# STB_LightSensors.net
KiCad netlist of a schematic drawn in Altium Designer
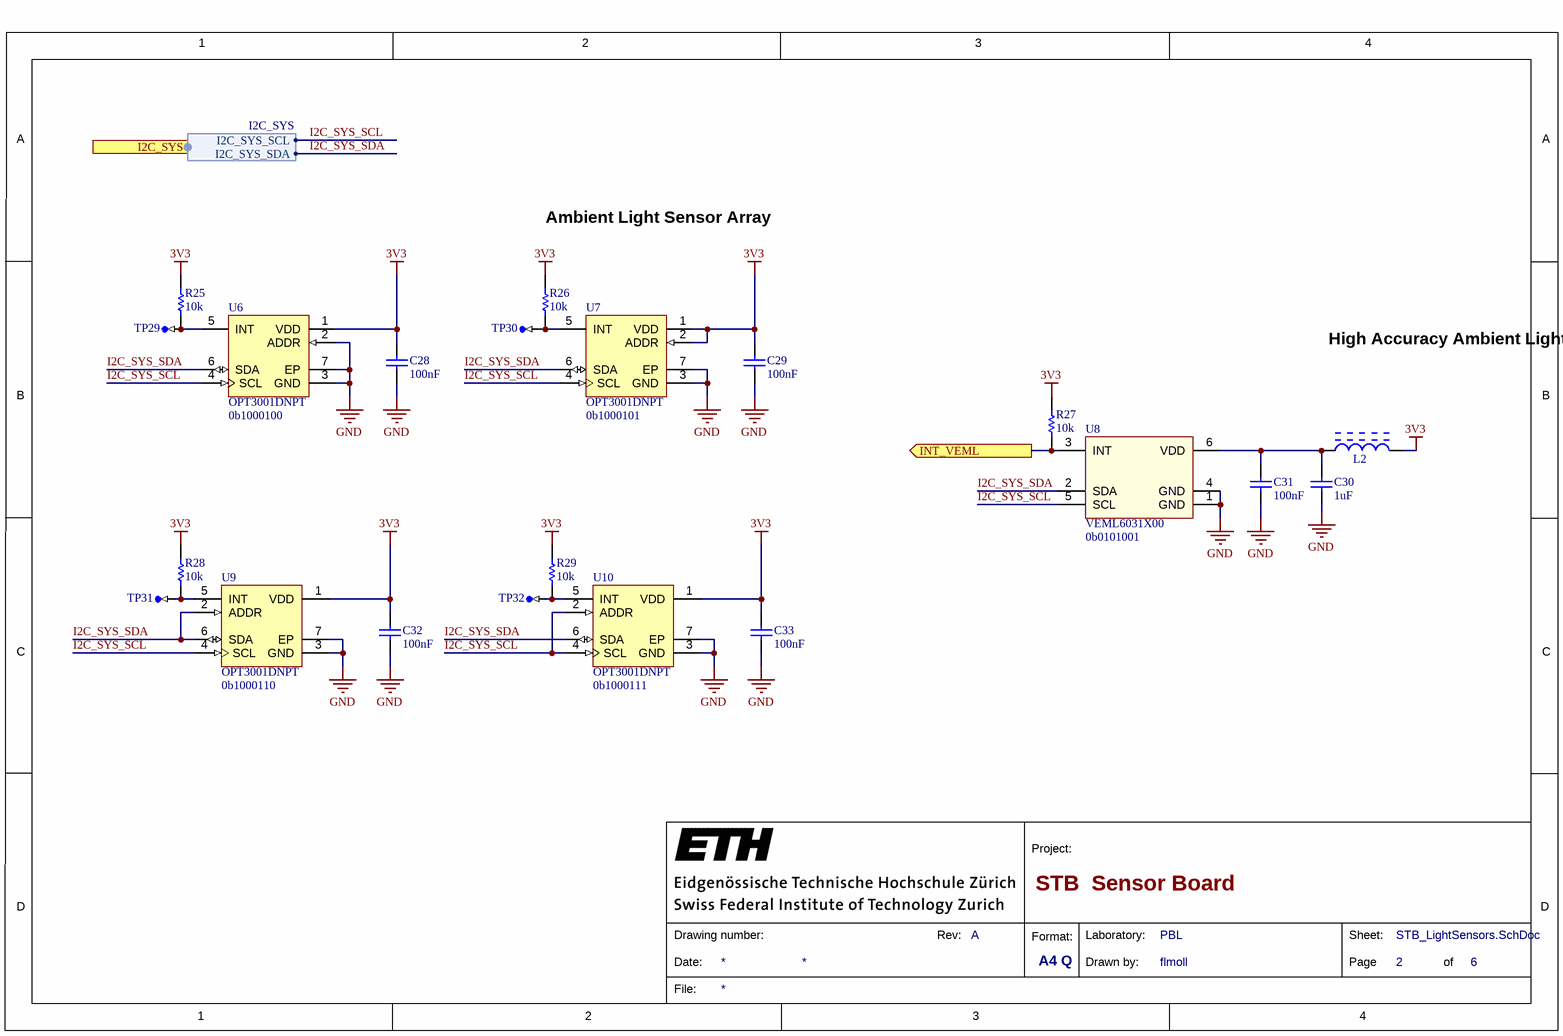
[diagram p0: STB_LightSensors.SchDoc]

(export (version "E")
  (design (tool "Eeschema 10.0.6"))
  (components
    (comp (ref "C28")
      (value "100nF")
      (footprint "CAPC1050X55X23LL05T13")
      (description "Chip Capacitor, 100 nF, +/- 10%, 16 V, -55 to 125 degC, 0402 (1005 Metric), RoHS, Tape and Reel")
      (fields
        (field (name "MANUFACTURER") "Samsung Electro-Mechanics")
        (field (name "MANUFACTURER PART NUMBER") "CL05B104KO5NNNC")
      )
      (libsource (lib "Altium Content Vault") (part "CAP-NP-2"))
    )
    (comp (ref "C29")
      (value "100nF")
      (footprint "CAPC1050X55X23LL05T13")
      (description "Chip Capacitor, 100 nF, +/- 10%, 16 V, -55 to 125 degC, 0402 (1005 Metric), RoHS, Tape and Reel")
      (fields
        (field (name "MANUFACTURER") "Samsung Electro-Mechanics")
        (field (name "MANUFACTURER PART NUMBER") "CL05B104KO5NNNC")
      )
      (libsource (lib "Altium Content Vault") (part "CAP-NP-2"))
    )
    (comp (ref "C30")
      (value "1uF")
      (footprint "CAPC1608X90X35LL15T15")
      (fields (field (name "MANUFACTURER") "Kemet") (field (name "PART NUMBER") "C0603C105K4RACTU"))
      (libsource (lib "Altium Content Vault") (part "CAP"))
    )
    (comp (ref "C31")
      (value "100nF")
      (footprint "CAPC1050X55X23LL05T13")
      (description "Chip Capacitor, 100 nF, +/- 10%, 16 V, -55 to 125 degC, 0402 (1005 Metric), RoHS, Tape and Reel")
      (fields
        (field (name "MANUFACTURER") "Samsung Electro-Mechanics")
        (field (name "MANUFACTURER PART NUMBER") "CL05B104KO5NNNC")
      )
      (libsource (lib "Altium Content Vault") (part "CAP-NP-2"))
    )
    (comp (ref "C32")
      (value "100nF")
      (footprint "CAPC1050X55X23LL05T13")
      (description "Chip Capacitor, 100 nF, +/- 10%, 16 V, -55 to 125 degC, 0402 (1005 Metric), RoHS, Tape and Reel")
      (fields
        (field (name "MANUFACTURER") "Samsung Electro-Mechanics")
        (field (name "MANUFACTURER PART NUMBER") "CL05B104KO5NNNC")
      )
      (libsource (lib "Altium Content Vault") (part "CAP-NP-2"))
    )
    (comp (ref "C33")
      (value "100nF")
      (footprint "CAPC1050X55X23LL05T13")
      (description "Chip Capacitor, 100 nF, +/- 10%, 16 V, -55 to 125 degC, 0402 (1005 Metric), RoHS, Tape and Reel")
      (fields
        (field (name "MANUFACTURER") "Samsung Electro-Mechanics")
        (field (name "MANUFACTURER PART NUMBER") "CL05B104KO5NNNC")
      )
      (libsource (lib "Altium Content Vault") (part "CAP-NP-2"))
    )
    (comp (ref "L2")
      (value "LI0402E300R-10")
      (footprint "INDC1005X07L")
      (description "30 Ohm 1 Power, Signal Line Ferrite Bead 0402 (1005 Metric) 500mA 300 mOhm Max DCR")
      (fields (field (name "MANUFACTURER") "Laird-Signal Integrity Products"))
      (libsource (lib "ETHZ Vault") (part "Ferrite Bead"))
    )
    (comp (ref "R25")
      (value "10k")
      (footprint "RESC1005X40X25LL05T05")
      (description "Chip Resistor, 10 KOhm, +/- 1%, 0.1 W, -55 to 155 degC, 0402 (1005 Metric), RoHS, Tape and Reel")
      (fields (field (name "TOLERANCE") "1%") (field (name "MANUFACTURER") "Panasonic"))
      (libsource (lib "Altium Content Vault") (part "RES-2"))
    )
    (comp (ref "R26")
      (value "10k")
      (footprint "RESC1005X40X25LL05T05")
      (description "Chip Resistor, 10 KOhm, +/- 1%, 0.1 W, -55 to 155 degC, 0402 (1005 Metric), RoHS, Tape and Reel")
      (fields (field (name "TOLERANCE") "1%") (field (name "MANUFACTURER") "Panasonic"))
      (libsource (lib "Altium Content Vault") (part "RES-2"))
    )
    (comp (ref "R27")
      (value "10k")
      (footprint "RESC1005X40X25LL05T05")
      (description "Chip Resistor, 10 KOhm, +/- 1%, 0.1 W, -55 to 155 degC, 0402 (1005 Metric), RoHS, Tape and Reel")
      (fields (field (name "TOLERANCE") "1%") (field (name "MANUFACTURER") "Panasonic"))
      (libsource (lib "Altium Content Vault") (part "RES-2"))
    )
    (comp (ref "R28")
      (value "10k")
      (footprint "RESC1005X40X25LL05T05")
      (description "Chip Resistor, 10 KOhm, +/- 1%, 0.1 W, -55 to 155 degC, 0402 (1005 Metric), RoHS, Tape and Reel")
      (fields (field (name "TOLERANCE") "1%") (field (name "MANUFACTURER") "Panasonic"))
      (libsource (lib "Altium Content Vault") (part "RES-2"))
    )
    (comp (ref "R29")
      (value "10k")
      (footprint "RESC1005X40X25LL05T05")
      (description "Chip Resistor, 10 KOhm, +/- 1%, 0.1 W, -55 to 155 degC, 0402 (1005 Metric), RoHS, Tape and Reel")
      (fields (field (name "TOLERANCE") "1%") (field (name "MANUFACTURER") "Panasonic"))
      (libsource (lib "Altium Content Vault") (part "RES-2"))
    )
    (comp (ref "TP29")
      (value "testPoint_1mm")
      (footprint "TP-SM-C-100")
      (description "testPoint 1mm")
      (libsource (lib "STB_Schlib") (part "testPoint_1mm"))
    )
    (comp (ref "TP30")
      (value "testPoint_1mm")
      (footprint "TP-SM-C-100")
      (description "testPoint 1mm")
      (libsource (lib "STB_Schlib") (part "testPoint_1mm"))
    )
    (comp (ref "TP31")
      (value "testPoint_1mm")
      (footprint "TP-SM-C-100")
      (description "testPoint 1mm")
      (libsource (lib "STB_Schlib") (part "testPoint_1mm"))
    )
    (comp (ref "TP32")
      (value "testPoint_1mm")
      (footprint "TP-SM-C-100")
      (description "testPoint 1mm")
      (libsource (lib "STB_Schlib") (part "testPoint_1mm"))
    )
    (comp (ref "U6")
      (value "OPT3001DNPT")
      (footprint "DNP0006A")
      (fields (field (name "MANUFACTURER") "Texas Instruments"))
      (libsource (lib "Altium Content Vault") (part "TI-OPT3001-DNP-6"))
    )
    (comp (ref "U7")
      (value "OPT3001DNPT")
      (footprint "DNP0006A")
      (fields (field (name "MANUFACTURER") "Texas Instruments"))
      (libsource (lib "Altium Content Vault") (part "TI-OPT3001-DNP-6"))
    )
    (comp (ref "U8")
      (value "VEML6031X00")
      (footprint "6-SMD - No Thermal Pad_2")
      (description "Ambient Light Sensor, I²C 6-SMD, No Lead")
      (fields
        (field (name "MFR") "Vishay Semiconductor Opto Division")
        (field (name "MANUFACTURER") "Vishay")
      )
      (libsource (lib "ETHZ Vault") (part "VEML60311X00"))
    )
    (comp (ref "U9")
      (value "OPT3001DNPT")
      (footprint "DNP0006A")
      (fields (field (name "MANUFACTURER") "Texas Instruments"))
      (libsource (lib "") (part "TI-OPT3001-DNP-6_1"))
    )
    (comp (ref "U10")
      (value "OPT3001DNPT")
      (footprint "DNP0006A")
      (fields (field (name "MANUFACTURER") "Texas Instruments"))
      (libsource (lib "") (part "TI-OPT3001-DNP-6_1"))
    )
  )
  (nets
    (net (code "2") (name "/I2C_SYS_SCL") (class "Default")
      (node (ref "U10") (pin "2") (pinfunction "ADDR_2") (pintype "input"))
      (node (ref "U10") (pin "4") (pinfunction "SCL_4") (pintype "input"))
      (node (ref "U6") (pin "4") (pinfunction "SCL_4") (pintype "input"))
      (node (ref "U7") (pin "4") (pinfunction "SCL_4") (pintype "input"))
      (node (ref "U8") (pin "5") (pinfunction "SCL_5") (pintype "passive"))
      (node (ref "U9") (pin "4") (pinfunction "SCL_4") (pintype "input"))
    )
    (net (code "3") (name "/I2C_SYS_SDA") (class "Default")
      (node (ref "U10") (pin "6") (pinfunction "SDA_6") (pintype "bidirectional"))
      (node (ref "U6") (pin "6") (pinfunction "SDA_6") (pintype "bidirectional"))
      (node (ref "U7") (pin "6") (pinfunction "SDA_6") (pintype "bidirectional"))
      (node (ref "U8") (pin "2") (pinfunction "SDA_2") (pintype "passive"))
      (node (ref "U9") (pin "2") (pinfunction "ADDR_2") (pintype "input"))
      (node (ref "U9") (pin "6") (pinfunction "SDA_6") (pintype "bidirectional"))
    )
    (net (code "4") (name "/INT_VEML") (class "Default")
      (node (ref "R27") (pin "1") (pinfunction "1_1") (pintype "passive"))
      (node (ref "U8") (pin "3") (pinfunction "INT_3") (pintype "passive"))
    )
    (net (code "6") (name "3V3") (class "Default")
      (node (ref "C28") (pin "2") (pinfunction "2_2") (pintype "passive"))
      (node (ref "C29") (pin "2") (pinfunction "2_2") (pintype "passive"))
      (node (ref "C32") (pin "2") (pinfunction "2_2") (pintype "passive"))
      (node (ref "C33") (pin "2") (pinfunction "2_2") (pintype "passive"))
      (node (ref "L2") (pin "2") (pinfunction "2_2") (pintype "passive"))
      (node (ref "R25") (pin "2") (pinfunction "2_2") (pintype "passive"))
      (node (ref "R26") (pin "2") (pinfunction "2_2") (pintype "passive"))
      (node (ref "R27") (pin "2") (pinfunction "2_2") (pintype "passive"))
      (node (ref "R28") (pin "2") (pinfunction "2_2") (pintype "passive"))
      (node (ref "R29") (pin "2") (pinfunction "2_2") (pintype "passive"))
      (node (ref "U10") (pin "1") (pinfunction "VDD_1") (pintype "power_in"))
      (node (ref "U6") (pin "1") (pinfunction "VDD_1") (pintype "power_in"))
      (node (ref "U7") (pin "1") (pinfunction "VDD_1") (pintype "power_in"))
      (node (ref "U7") (pin "2") (pinfunction "ADDR_2") (pintype "input"))
      (node (ref "U9") (pin "1") (pinfunction "VDD_1") (pintype "power_in"))
    )
    (net (code "7") (name "GND") (class "Default")
      (node (ref "C28") (pin "1") (pinfunction "1_1") (pintype "passive"))
      (node (ref "C29") (pin "1") (pinfunction "1_1") (pintype "passive"))
      (node (ref "C30") (pin "1") (pinfunction "1_1") (pintype "passive"))
      (node (ref "C31") (pin "1") (pinfunction "1_1") (pintype "passive"))
      (node (ref "C32") (pin "1") (pinfunction "1_1") (pintype "passive"))
      (node (ref "C33") (pin "1") (pinfunction "1_1") (pintype "passive"))
      (node (ref "U10") (pin "3") (pinfunction "GND_3") (pintype "power_in"))
      (node (ref "U10") (pin "7") (pinfunction "EP_7") (pintype "passive"))
      (node (ref "U6") (pin "2") (pinfunction "ADDR_2") (pintype "input"))
      (node (ref "U6") (pin "3") (pinfunction "GND_3") (pintype "power_in"))
      (node (ref "U6") (pin "7") (pinfunction "EP_7") (pintype "passive"))
      (node (ref "U7") (pin "3") (pinfunction "GND_3") (pintype "power_in"))
      (node (ref "U7") (pin "7") (pinfunction "EP_7") (pintype "passive"))
      (node (ref "U8") (pin "1") (pinfunction "GND_1") (pintype "passive"))
      (node (ref "U8") (pin "4") (pinfunction "GND_4") (pintype "passive"))
      (node (ref "U9") (pin "3") (pinfunction "GND_3") (pintype "power_in"))
      (node (ref "U9") (pin "7") (pinfunction "EP_7") (pintype "passive"))
    )
    (net (code "8") (name "Net-(U6-INT)") (class "Default")
      (node (ref "R25") (pin "1") (pinfunction "1_1") (pintype "passive"))
      (node (ref "TP29") (pin "TP") (pinfunction "TP_TP") (pintype "input"))
      (node (ref "U6") (pin "5") (pinfunction "INT_5") (pintype "open_collector"))
    )
    (net (code "9") (name "Net-(U7-INT)") (class "Default")
      (node (ref "R26") (pin "1") (pinfunction "1_1") (pintype "passive"))
      (node (ref "TP30") (pin "TP") (pinfunction "TP_TP") (pintype "input"))
      (node (ref "U7") (pin "5") (pinfunction "INT_5") (pintype "open_collector"))
    )
    (net (code "10") (name "Net-(U8-VDD)") (class "Default")
      (node (ref "C30") (pin "2") (pinfunction "2_2") (pintype "passive"))
      (node (ref "C31") (pin "2") (pinfunction "2_2") (pintype "passive"))
      (node (ref "L2") (pin "1") (pinfunction "1_1") (pintype "passive"))
      (node (ref "U8") (pin "6") (pinfunction "VDD_6") (pintype "passive"))
    )
    (net (code "11") (name "Net-(U9-INT)") (class "Default")
      (node (ref "R28") (pin "1") (pinfunction "1_1") (pintype "passive"))
      (node (ref "TP31") (pin "TP") (pinfunction "TP_TP") (pintype "input"))
      (node (ref "U9") (pin "5") (pinfunction "INT_5") (pintype "open_collector"))
    )
    (net (code "12") (name "Net-(U10-INT)") (class "Default")
      (node (ref "R29") (pin "1") (pinfunction "1_1") (pintype "passive"))
      (node (ref "TP32") (pin "TP") (pinfunction "TP_TP") (pintype "input"))
      (node (ref "U10") (pin "5") (pinfunction "INT_5") (pintype "open_collector"))
    )
  )
)
